# power_supply.net
KiCad netlist of a schematic drawn in Altium Designer
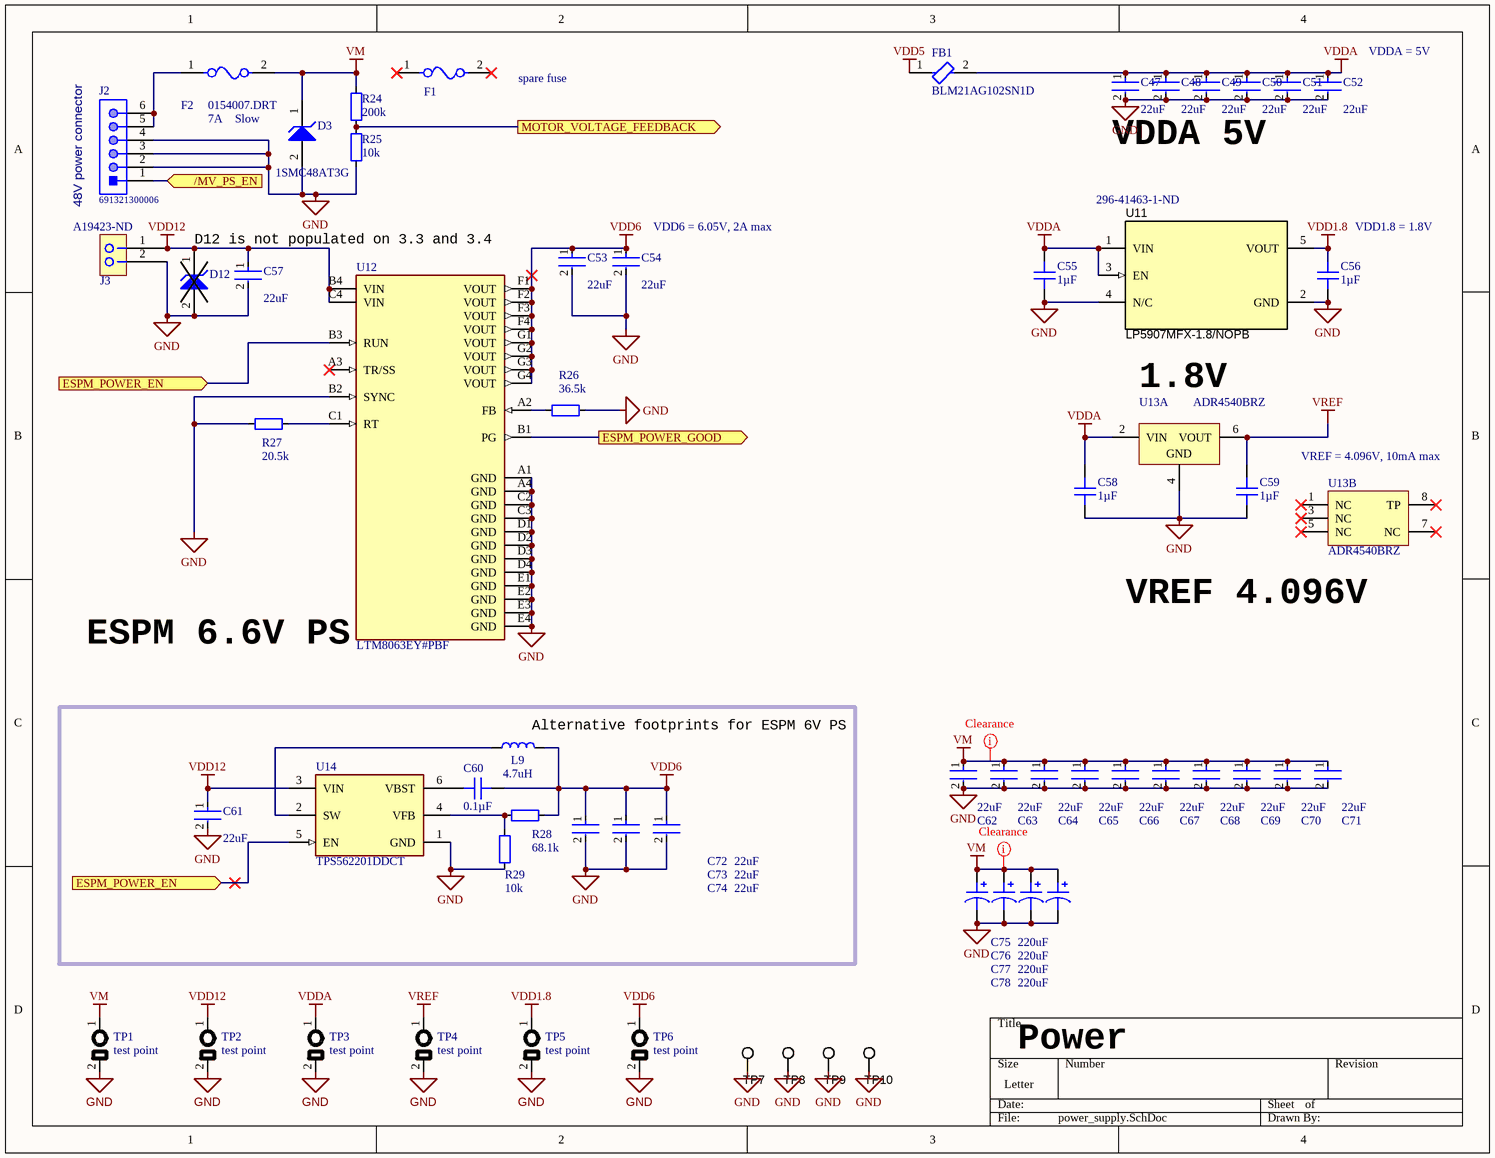
[diagram p0: power_supply.SchDoc]

(export (version "E")
  (design (tool "Eeschema 10.0.6"))
  (components
    (comp (ref "C47")
      (value "CL32B226MOJNNNE")
      (footprint "FP-CL32-IPC_B")
      (description "Cap Ceramic 22uF 16V X7R ±20% SMD 1210 +125°C Embossed T/R")
      (fields (field (name "CAPACITANCE") "22uF") (field (name "TOLERANCE") "20%"))
      (libsource (lib "Altium Content Vault") (part "b4654b650e69147ec39a6b967a45e02"))
    )
    (comp (ref "C48")
      (value "CL32B226MOJNNNE")
      (footprint "FP-CL32-IPC_B")
      (description "Cap Ceramic 22uF 16V X7R ±20% SMD 1210 +125°C Embossed T/R")
      (fields (field (name "CAPACITANCE") "22uF") (field (name "TOLERANCE") "20%"))
      (libsource (lib "Altium Content Vault") (part "b4654b650e69147ec39a6b967a45e02"))
    )
    (comp (ref "C49")
      (value "CL32B226MOJNNNE")
      (footprint "FP-CL32-IPC_B")
      (description "Cap Ceramic 22uF 16V X7R ±20% SMD 1210 +125°C Embossed T/R")
      (fields (field (name "CAPACITANCE") "22uF") (field (name "TOLERANCE") "20%"))
      (libsource (lib "Altium Content Vault") (part "b4654b650e69147ec39a6b967a45e02"))
    )
    (comp (ref "C50")
      (value "CL32B226MOJNNNE")
      (footprint "FP-CL32-IPC_B")
      (description "Cap Ceramic 22uF 16V X7R ±20% SMD 1210 +125°C Embossed T/R")
      (fields (field (name "CAPACITANCE") "22uF") (field (name "TOLERANCE") "20%"))
      (libsource (lib "Altium Content Vault") (part "b4654b650e69147ec39a6b967a45e02"))
    )
    (comp (ref "C51")
      (value "CL32B226MOJNNNE")
      (footprint "FP-CL32-IPC_B")
      (description "Cap Ceramic 22uF 16V X7R ±20% SMD 1210 +125°C Embossed T/R")
      (fields (field (name "CAPACITANCE") "22uF") (field (name "TOLERANCE") "20%"))
      (libsource (lib "Altium Content Vault") (part "b4654b650e69147ec39a6b967a45e02"))
    )
    (comp (ref "C52")
      (value "CL32B226MOJNNNE")
      (footprint "FP-CL32-IPC_B")
      (description "Cap Ceramic 22uF 16V X7R ±20% SMD 1210 +125°C Embossed T/R")
      (fields (field (name "CAPACITANCE") "22uF") (field (name "TOLERANCE") "20%"))
      (libsource (lib "Altium Content Vault") (part "b4654b650e69147ec39a6b967a45e02"))
    )
    (comp (ref "C53")
      (value "CL32B226MOJNNNE")
      (footprint "FP-CL32-IPC_B")
      (description "Cap Ceramic 22uF 16V X7R ±20% SMD 1210 +125°C Embossed T/R")
      (fields (field (name "CAPACITANCE") "22uF") (field (name "TOLERANCE") "20%"))
      (libsource (lib "Altium Content Vault") (part "b4654b650e69147ec39a6b967a45e02"))
    )
    (comp (ref "C54")
      (value "CL32B226MOJNNNE")
      (footprint "FP-CL32-IPC_B")
      (description "Cap Ceramic 22uF 16V X7R ±20% SMD 1210 +125°C Embossed T/R")
      (fields (field (name "CAPACITANCE") "22uF") (field (name "TOLERANCE") "20%"))
      (libsource (lib "Altium Content Vault") (part "b4654b650e69147ec39a6b967a45e02"))
    )
    (comp (ref "C55")
      (value "1µF")
      (footprint "FP-GRM155-0_05-IPC_B")
      (description "CAP CER 1UF 6.3V X7R 0402")
      (fields
        (field (name "PART NUMBER") "GRM155R70J105KA12J")
        (field (name "MANUFACTURER") "Murata Electronics")
      )
      (libsource (lib "Celestial Altium Library - altium_library") (part "Capacitor"))
    )
    (comp (ref "C56")
      (value "1µF")
      (footprint "FP-GRM155-0_05-IPC_B")
      (description "CAP CER 1UF 6.3V X7R 0402")
      (fields
        (field (name "PART NUMBER") "GRM155R70J105KA12J")
        (field (name "MANUFACTURER") "Murata Electronics")
      )
      (libsource (lib "Celestial Altium Library - altium_library") (part "Capacitor"))
    )
    (comp (ref "C57")
      (value "CL32B226MOJNNNE")
      (footprint "FP-CL32-IPC_B")
      (description "Cap Ceramic 22uF 16V X7R ±20% SMD 1210 +125°C Embossed T/R")
      (fields (field (name "CAPACITANCE") "22uF") (field (name "TOLERANCE") "20%"))
      (libsource (lib "Altium Content Vault") (part "b4654b650e69147ec39a6b967a45e02"))
    )
    (comp (ref "C58")
      (value "1µF")
      (footprint "FP-GRM155-0_05-IPC_B")
      (description "CAP CER 1UF 6.3V X7R 0402")
      (fields
        (field (name "PART NUMBER") "GRM155R70J105KA12J")
        (field (name "MANUFACTURER") "Murata Electronics")
      )
      (libsource (lib "Celestial Altium Library - altium_library") (part "Capacitor"))
    )
    (comp (ref "C59")
      (value "1µF")
      (footprint "FP-GRM155-0_05-IPC_B")
      (description "CAP CER 1UF 6.3V X7R 0402")
      (fields
        (field (name "PART NUMBER") "GRM155R70J105KA12J")
        (field (name "MANUFACTURER") "Murata Electronics")
      )
      (libsource (lib "Celestial Altium Library - altium_library") (part "Capacitor"))
    )
    (comp (ref "C60")
      (value "0.1µF")
      (footprint "FP-GRM155-0_05-IPC_B")
      (description "CAP CER 0.1UF 25V X7R 0402")
      (fields (field (name "MANUFACTURER") "AVX Corporation") (field (name "PART NUMBER") "04023C104KAT2A"))
      (libsource (lib "Celestial Altium Library - altium_library") (part "Capacitor"))
    )
    (comp (ref "C61")
      (value "CL32B226MOJNNNE")
      (footprint "FP-CL32-IPC_B")
      (description "Cap Ceramic 22uF 16V X7R ±20% SMD 1210 +125°C Embossed T/R")
      (fields (field (name "CAPACITANCE") "22uF") (field (name "TOLERANCE") "20%"))
      (libsource (lib "Altium Content Vault") (part "b4654b650e69147ec39a6b967a45e02"))
    )
    (comp (ref "C62")
      (value "KRM55WR72A226MH01L")
      (footprint "FP-KRM55W-6_1_5_3_6_7_1_2-MFG")
      (description "CAP CER 22UF 100V X7R SMD")
      (fields (field (name "CAPACITANCE") "22uF") (field (name "TOLERANCE") "20%"))
      (libsource (lib "Altium Content Vault") (part "02cd4be3c70576c341d710602a673aa"))
    )
    (comp (ref "C63")
      (value "KRM55WR72A226MH01L")
      (footprint "FP-KRM55W-6_1_5_3_6_7_1_2-MFG")
      (description "CAP CER 22UF 100V X7R SMD")
      (fields (field (name "CAPACITANCE") "22uF") (field (name "TOLERANCE") "20%"))
      (libsource (lib "Altium Content Vault") (part "02cd4be3c70576c341d710602a673aa"))
    )
    (comp (ref "C64")
      (value "KRM55WR72A226MH01L")
      (footprint "FP-KRM55W-6_1_5_3_6_7_1_2-MFG")
      (description "CAP CER 22UF 100V X7R SMD")
      (fields (field (name "CAPACITANCE") "22uF") (field (name "TOLERANCE") "20%"))
      (libsource (lib "Altium Content Vault") (part "02cd4be3c70576c341d710602a673aa"))
    )
    (comp (ref "C65")
      (value "KRM55WR72A226MH01L")
      (footprint "FP-KRM55W-6_1_5_3_6_7_1_2-MFG")
      (description "CAP CER 22UF 100V X7R SMD")
      (fields (field (name "CAPACITANCE") "22uF") (field (name "TOLERANCE") "20%"))
      (libsource (lib "Altium Content Vault") (part "02cd4be3c70576c341d710602a673aa"))
    )
    (comp (ref "C66")
      (value "KRM55WR72A226MH01L")
      (footprint "FP-KRM55W-6_1_5_3_6_7_1_2-MFG")
      (description "CAP CER 22UF 100V X7R SMD")
      (fields (field (name "CAPACITANCE") "22uF") (field (name "TOLERANCE") "20%"))
      (libsource (lib "Altium Content Vault") (part "02cd4be3c70576c341d710602a673aa"))
    )
    (comp (ref "C67")
      (value "KRM55WR72A226MH01L")
      (footprint "FP-KRM55W-6_1_5_3_6_7_1_2-MFG")
      (description "CAP CER 22UF 100V X7R SMD")
      (fields (field (name "CAPACITANCE") "22uF") (field (name "TOLERANCE") "20%"))
      (libsource (lib "Altium Content Vault") (part "02cd4be3c70576c341d710602a673aa"))
    )
    (comp (ref "C68")
      (value "KRM55WR72A226MH01L")
      (footprint "FP-KRM55W-6_1_5_3_6_7_1_2-MFG")
      (description "CAP CER 22UF 100V X7R SMD")
      (fields (field (name "CAPACITANCE") "22uF") (field (name "TOLERANCE") "20%"))
      (libsource (lib "Altium Content Vault") (part "02cd4be3c70576c341d710602a673aa"))
    )
    (comp (ref "C69")
      (value "KRM55WR72A226MH01L")
      (footprint "FP-KRM55W-6_1_5_3_6_7_1_2-MFG")
      (description "CAP CER 22UF 100V X7R SMD")
      (fields (field (name "CAPACITANCE") "22uF") (field (name "TOLERANCE") "20%"))
      (libsource (lib "Altium Content Vault") (part "02cd4be3c70576c341d710602a673aa"))
    )
    (comp (ref "C70")
      (value "KRM55WR72A226MH01L")
      (footprint "FP-KRM55W-6_1_5_3_6_7_1_2-MFG")
      (description "CAP CER 22UF 100V X7R SMD")
      (fields (field (name "CAPACITANCE") "22uF") (field (name "TOLERANCE") "20%"))
      (libsource (lib "Altium Content Vault") (part "02cd4be3c70576c341d710602a673aa"))
    )
    (comp (ref "C71")
      (value "KRM55WR72A226MH01L")
      (footprint "FP-KRM55W-6_1_5_3_6_7_1_2-MFG")
      (description "CAP CER 22UF 100V X7R SMD")
      (fields (field (name "CAPACITANCE") "22uF") (field (name "TOLERANCE") "20%"))
      (libsource (lib "Altium Content Vault") (part "02cd4be3c70576c341d710602a673aa"))
    )
    (comp (ref "C72")
      (value "CL32B226MOJNNNE")
      (footprint "FP-CL32-IPC_B")
      (description "Cap Ceramic 22uF 16V X7R ±20% SMD 1210 +125°C Embossed T/R")
      (fields (field (name "CAPACITANCE") "22uF") (field (name "TOLERANCE") "20%"))
      (libsource (lib "Altium Content Vault") (part "b4654b650e69147ec39a6b967a45e02"))
    )
    (comp (ref "C73")
      (value "CL32B226MOJNNNE")
      (footprint "FP-CL32-IPC_B")
      (description "Cap Ceramic 22uF 16V X7R ±20% SMD 1210 +125°C Embossed T/R")
      (fields (field (name "CAPACITANCE") "22uF") (field (name "TOLERANCE") "20%"))
      (libsource (lib "Altium Content Vault") (part "b4654b650e69147ec39a6b967a45e02"))
    )
    (comp (ref "C74")
      (value "CL32B226MOJNNNE")
      (footprint "FP-CL32-IPC_B")
      (description "Cap Ceramic 22uF 16V X7R ±20% SMD 1210 +125°C Embossed T/R")
      (fields (field (name "CAPACITANCE") "22uF") (field (name "TOLERANCE") "20%"))
      (libsource (lib "Altium Content Vault") (part "b4654b650e69147ec39a6b967a45e02"))
    )
    (comp (ref "C75")
      (value "~")
      (footprint "100TXW220MEFC10X40_horizontal")
      (description "TXW Series 100 V 220 uF 10 x 40 mm LS=5 mm Radial Aluminum Electrolytic")
      (fields
        (field (name "MANUFACTURER") "Rubycon")
        (field (name "MANUFACTURER PART NUMBER") "100TXW220MEFC10X40")
        (field (name "CAPACITANCE") "220uF")
      )
      (libsource (lib "dvrk-s-pwm_2") (part "Polarised Capacitor"))
    )
    (comp (ref "C76")
      (value "~")
      (footprint "100TXW220MEFC10X40_horizontal")
      (description "TXW Series 100 V 220 uF 10 x 40 mm LS=5 mm Radial Aluminum Electrolytic")
      (fields
        (field (name "MANUFACTURER") "Rubycon")
        (field (name "MANUFACTURER PART NUMBER") "100TXW220MEFC10X40")
        (field (name "CAPACITANCE") "220uF")
      )
      (libsource (lib "dvrk-s-pwm_2") (part "Polarised Capacitor"))
    )
    (comp (ref "C77")
      (value "~")
      (footprint "100TXW220MEFC10X40_horizontal")
      (description "TXW Series 100 V 220 uF 10 x 40 mm LS=5 mm Radial Aluminum Electrolytic")
      (fields
        (field (name "MANUFACTURER") "Rubycon")
        (field (name "MANUFACTURER PART NUMBER") "100TXW220MEFC10X40")
        (field (name "CAPACITANCE") "220uF")
      )
      (libsource (lib "dvrk-s-pwm_2") (part "Polarised Capacitor"))
    )
    (comp (ref "C78")
      (value "~")
      (footprint "100TXW220MEFC10X40_horizontal")
      (description "TXW Series 100 V 220 uF 10 x 40 mm LS=5 mm Radial Aluminum Electrolytic")
      (fields
        (field (name "MANUFACTURER") "Rubycon")
        (field (name "MANUFACTURER PART NUMBER") "100TXW220MEFC10X40")
        (field (name "CAPACITANCE") "220uF")
      )
      (libsource (lib "dvrk-s-pwm_2") (part "Polarised Capacitor"))
    )
    (comp (ref "D3")
      (value "1SMC48AT3G")
      (footprint "ONSC-SMC-2-403-03_V")
      (fields (field (name "MANUFACTURER") "On Semiconductor"))
      (libsource (lib "Altium Content Vault") (part "ONSC-K1A2-2"))
    )
    (comp (ref "D12")
      (value "1SMA12AT3G")
      (footprint "ONSC-SMA-2-403D-02_F_V")
      (description "400 W Peak Power Zener Transient Voltage Suppressor, 2-Pin SMA, Pb-Free, Tape and Reel")
      (fields (field (name "MANUFACTURER") "On Semiconductor"))
      (libsource (lib "Altium Content Vault") (part "ONSC-K1A2-2"))
    )
    (comp (ref "F1")
      (value "0154007.DRT")
      (footprint "FP-0154-MFG")
      (description "FUSE BRD MNT 7A 72VAC 60VDC 2SMD")
      (fields
        (field (name "OCTOPART") "https://octopart.com/0154007.drt-littelfuse-19644006")
        (field (name "MANUFACTURER") "Littelfuse Inc")
      )
      (libsource (lib "Altium Content Vault") (part "5bcf9b9f640e542cf0359d10258e979"))
    )
    (comp (ref "F2")
      (value "0154007.DRT")
      (footprint "FP-0154-MFG")
      (description "FUSE BRD MNT 7A 72VAC 60VDC 2SMD")
      (fields
        (field (name "FUSE CURRENT") "7A")
        (field (name "FUSE BLOW SPEED") "Slow")
        (field (name "OCTOPART") "https://octopart.com/0154007.drt-littelfuse-19644006")
        (field (name "MANUFACTURER") "Littelfuse Inc")
      )
      (libsource (lib "Altium Content Vault") (part "5bcf9b9f640e542cf0359d10258e979"))
    )
    (comp (ref "FB1")
      (value "BLM21AG102SN1D")
      (footprint "FP-BLM21-0_2-t0_85-e0_5-MFG")
      (description "Chip Ferrite Bead, 0805, 1000Ω @ 100MHz, 0.27Ω, 25%, 600mA")
      (fields (field (name "TOLERANCE") "25%"))
      (libsource (lib "Altium Content Vault") (part "5f30dd21d616792df468990f7003faa"))
    )
    (comp (ref "J2")
      (value "691321300006")
      (footprint "691321300006")
      (description "Serie 321 - 3.81mm Vertical PCB Header WR-TBL, 6 pin")
      (fields (field (name "MANUFACTURER") "Wurth Elektronik") (field (name "PUBLISHER") "WurthElektronik"))
      (libsource (lib "Altium Content Vault") (part "WE-CN-1P-M-R6"))
    )
    (comp (ref "J3")
      (value "Substitute with tyco 640457-2")
      (footprint "HDR-2x1-100")
      (fields
        (field (name "MANUFACTURER") "TE Connectivity")
        (field (name "MANUFACTURER PART NUMBER") "640457-2")
        (field (name "SUPPLIER PART NUMBER 1") "A19423-ND")
      )
      (libsource (lib "dvrk-s-pwm") (part "HEADER 2"))
    )
    (comp (ref "L9")
      (value "4.7uH")
      (footprint "INDUCTOR-XAL7030")
      (libsource (lib "FPGA") (part "INDUCTOR"))
    )
    (comp (ref "R24")
      (value "200k")
      (footprint "FP-CRCW0402-e3-IPC_B")
      (description "Resistor")
      (fields (field (name "Comment") "Res_0402"))
      (libsource (lib "SCH_Passive") (part "Res_0402"))
    )
    (comp (ref "R25")
      (value "10k")
      (footprint "FP-CRCW0402-e3-IPC_B")
      (description "Resistor")
      (fields (field (name "Comment") "Res_0402"))
      (libsource (lib "SCH_Passive") (part "Res_0402"))
    )
    (comp (ref "R26")
      (value "36.5k")
      (footprint "FP-CRCW0402-e3-IPC_B")
      (description "Resistor")
      (fields (field (name "Comment") "Res_0402"))
      (libsource (lib "") (part "Res_0402_1"))
    )
    (comp (ref "R27")
      (value "20.5k")
      (footprint "FP-CRCW0402-e3-IPC_B")
      (description "Resistor")
      (fields (field (name "Comment") "Res_0402"))
      (libsource (lib "") (part "Res_0402_1"))
    )
    (comp (ref "R28")
      (value "68.1k")
      (footprint "FP-CRCW0402-e3-IPC_B")
      (description "Resistor")
      (fields (field (name "Comment") "Res_0402"))
      (libsource (lib "") (part "Res_0402_1"))
    )
    (comp (ref "R29")
      (value "10k")
      (footprint "FP-CRCW0402-e3-IPC_B")
      (description "Resistor")
      (fields (field (name "Comment") "Res_0402"))
      (libsource (lib "SCH_Passive") (part "Res_0402"))
    )
    (comp (ref "TP1")
      (value "test point")
      (footprint "TP_GND")
      (libsource (lib "dvrk-s-pwm") (part "TP_GND"))
    )
    (comp (ref "TP2")
      (value "test point")
      (footprint "TP_GND")
      (libsource (lib "dvrk-s-pwm") (part "TP_GND"))
    )
    (comp (ref "TP3")
      (value "test point")
      (footprint "TP_GND")
      (libsource (lib "dvrk-s-pwm") (part "TP_GND"))
    )
    (comp (ref "TP4")
      (value "test point")
      (footprint "TP_GND")
      (libsource (lib "dvrk-s-pwm") (part "TP_GND"))
    )
    (comp (ref "TP5")
      (value "test point")
      (footprint "TP_GND")
      (libsource (lib "dvrk-s-pwm") (part "TP_GND"))
    )
    (comp (ref "TP6")
      (value "test point")
      (footprint "TP_GND")
      (libsource (lib "dvrk-s-pwm") (part "TP_GND"))
    )
    (comp (ref "TP7")
      (value "5016")
      (footprint "Testpoint_Keystone_Compact")
      (description "Test Point, Compact, SMT")
      (fields (field (name "MANUFACTURER") "Keystone") (field (name "PUBLISHER") "Texas Instruments"))
      (libsource (lib "dvrk-s-pwm") (part "5016"))
    )
    (comp (ref "TP8")
      (value "5016")
      (footprint "Testpoint_Keystone_Compact")
      (description "Test Point, Compact, SMT")
      (fields (field (name "MANUFACTURER") "Keystone") (field (name "PUBLISHER") "Texas Instruments"))
      (libsource (lib "dvrk-s-pwm") (part "5016"))
    )
    (comp (ref "TP9")
      (value "5016")
      (footprint "Testpoint_Keystone_Compact")
      (description "Test Point, Compact, SMT")
      (fields (field (name "MANUFACTURER") "Keystone") (field (name "PUBLISHER") "Texas Instruments"))
      (libsource (lib "dvrk-s-pwm") (part "5016"))
    )
    (comp (ref "TP10")
      (value "5016")
      (footprint "Testpoint_Keystone_Compact")
      (description "Test Point, Compact, SMT")
      (fields (field (name "MANUFACTURER") "Keystone") (field (name "PUBLISHER") "Texas Instruments"))
      (libsource (lib "dvrk-s-pwm") (part "5016"))
    )
    (comp (ref "U11")
      (value "LP5907MFX-1.8/NOPB")
      (footprint "DBV0005A_N")
      (description "Ultra Low Noise, 250mA Linear Regulator")
      (fields
        (field (name "MANUFACTURER") "Texas Instruments")
        (field (name "SUPPLIER PART NUMBER 1") "296-41463-1-ND")
        (field (name "SYMBOLCREATOR") "a0799628")
        (field (name "PUBLISHER") "Texas Instruments")
      )
      (libsource (lib "dvrk-s-pwm") (part "LP5907MFX-3.3/NOPB"))
    )
    (comp (ref "U12")
      (value "LTM8063EY#PBF")
      (footprint "FP-BGA-28-05-08-1517-MFG")
      (description "DC DC CONVERTER 0.8-15V")
      (fields
        (field (name "OCTOPART") "https://octopart.com/ltm8063ey%23pbf-analog+devices-88947122")
        (field (name "MANUFACTURER") "Analog Devices")
      )
      (libsource (lib "Altium Content Vault") (part "b54610757978533170b9aabd89f6d2c"))
    )
    (comp (ref "U13")
      (value "ADR4540BRZ")
      (footprint "ADI-R-8_M")
      (fields (field (name "MANUFACTURER") "Analog Devices"))
      (libsource (lib "Altium Content Vault") (part "ADI-ADR45xx-R-8"))
    )
    (comp (ref "U14")
      (value "TPS562201DDCT")
      (footprint "FP-DDC0006A-IPC_C")
      (description "IC REG BUCK ADJ 2A TSOT23-6")
      (fields
        (field (name "OCTOPART") "https://octopart.com/tps562201ddct-texas+instruments-68059584")
        (field (name "MANUFACTURER") "Texas Instruments")
      )
      (libsource (lib "Altium Content Vault") (part "06d79c7d29d628b4662ce6edb459819"))
    )
  )
  (nets
    (net (code "1") (name "/ESPM_POWER_EN") (class "Default")
      (node (ref "U12") (pin "B3") (pinfunction "RUN_B3") (pintype "input"))
      (node (ref "U14") (pin "5") (pinfunction "EN_5") (pintype "input"))
    )
    (net (code "2") (name "/ESPM_POWER_GOOD") (class "Default")
      (node (ref "U12") (pin "B1") (pinfunction "PG_B1") (pintype "output"))
    )
    (net (code "3") (name "/MOTOR_VOLTAGE_FEEDBACK") (class "Default")
      (node (ref "R24") (pin "1") (pinfunction "1_1") (pintype "passive"))
      (node (ref "R25") (pin "2") (pinfunction "2_2") (pintype "passive"))
    )
    (net (code "4") (name "/{slash}MV_PS_EN") (class "Default")
      (node (ref "J2") (pin "1") (pinfunction "1_1") (pintype "passive"))
    )
    (net (code "5") (name "GND") (class "Default")
      (node (ref "C47") (pin "2") (pinfunction "2_2") (pintype "passive"))
      (node (ref "C48") (pin "2") (pinfunction "2_2") (pintype "passive"))
      (node (ref "C49") (pin "2") (pinfunction "2_2") (pintype "passive"))
      (node (ref "C50") (pin "2") (pinfunction "2_2") (pintype "passive"))
      (node (ref "C51") (pin "2") (pinfunction "2_2") (pintype "passive"))
      (node (ref "C52") (pin "2") (pinfunction "2_2") (pintype "passive"))
      (node (ref "C53") (pin "2") (pinfunction "2_2") (pintype "passive"))
      (node (ref "C54") (pin "2") (pinfunction "2_2") (pintype "passive"))
      (node (ref "C55") (pin "1") (pinfunction "1_1") (pintype "passive"))
      (node (ref "C56") (pin "1") (pinfunction "1_1") (pintype "passive"))
      (node (ref "C57") (pin "2") (pinfunction "2_2") (pintype "passive"))
      (node (ref "C58") (pin "1") (pinfunction "1_1") (pintype "passive"))
      (node (ref "C59") (pin "1") (pinfunction "1_1") (pintype "passive"))
      (node (ref "C61") (pin "2") (pinfunction "2_2") (pintype "passive"))
      (node (ref "C62") (pin "2") (pinfunction "2_2") (pintype "passive"))
      (node (ref "C63") (pin "2") (pinfunction "2_2") (pintype "passive"))
      (node (ref "C64") (pin "2") (pinfunction "2_2") (pintype "passive"))
      (node (ref "C65") (pin "2") (pinfunction "2_2") (pintype "passive"))
      (node (ref "C66") (pin "2") (pinfunction "2_2") (pintype "passive"))
      (node (ref "C67") (pin "2") (pinfunction "2_2") (pintype "passive"))
      (node (ref "C68") (pin "2") (pinfunction "2_2") (pintype "passive"))
      (node (ref "C69") (pin "2") (pinfunction "2_2") (pintype "passive"))
      (node (ref "C70") (pin "2") (pinfunction "2_2") (pintype "passive"))
      (node (ref "C71") (pin "2") (pinfunction "2_2") (pintype "passive"))
      (node (ref "C72") (pin "2") (pinfunction "2_2") (pintype "passive"))
      (node (ref "C73") (pin "2") (pinfunction "2_2") (pintype "passive"))
      (node (ref "C74") (pin "2") (pinfunction "2_2") (pintype "passive"))
      (node (ref "C75") (pin "2") (pinfunction "2_2") (pintype "passive"))
      (node (ref "C76") (pin "2") (pinfunction "2_2") (pintype "passive"))
      (node (ref "C77") (pin "2") (pinfunction "2_2") (pintype "passive"))
      (node (ref "C78") (pin "2") (pinfunction "2_2") (pintype "passive"))
      (node (ref "D12") (pin "2") (pinfunction "A_2") (pintype "passive"))
      (node (ref "D3") (pin "2") (pinfunction "A_2") (pintype "passive"))
      (node (ref "J2") (pin "2") (pinfunction "2_2") (pintype "passive"))
      (node (ref "J2") (pin "3") (pinfunction "3_3") (pintype "passive"))
      (node (ref "J2") (pin "4") (pinfunction "4_4") (pintype "passive"))
      (node (ref "J3") (pin "2") (pinfunction "2_2") (pintype "passive"))
      (node (ref "R25") (pin "1") (pinfunction "1_1") (pintype "passive"))
      (node (ref "R26") (pin "1") (pinfunction "1_1") (pintype "passive"))
      (node (ref "R27") (pin "2") (pinfunction "2_2") (pintype "passive"))
      (node (ref "R29") (pin "1") (pinfunction "1_1") (pintype "passive"))
      (node (ref "TP1") (pin "2") (pinfunction "gnd_2") (pintype "passive"))
      (node (ref "TP10") (pin "1") (pintype "passive"))
      (node (ref "TP2") (pin "2") (pinfunction "gnd_2") (pintype "passive"))
      (node (ref "TP3") (pin "2") (pinfunction "gnd_2") (pintype "passive"))
      (node (ref "TP4") (pin "2") (pinfunction "gnd_2") (pintype "passive"))
      (node (ref "TP5") (pin "2") (pinfunction "gnd_2") (pintype "passive"))
      (node (ref "TP6") (pin "2") (pinfunction "gnd_2") (pintype "passive"))
      (node (ref "TP7") (pin "1") (pintype "passive"))
      (node (ref "TP8") (pin "1") (pintype "passive"))
      (node (ref "TP9") (pin "1") (pintype "passive"))
      (node (ref "U11") (pin "2") (pinfunction "GND_2") (pintype "power_in"))
      (node (ref "U11") (pin "4") (pinfunction "N/C_4") (pintype "passive"))
      (node (ref "U12") (pin "A1") (pinfunction "GND_A1") (pintype "power_in"))
      (node (ref "U12") (pin "A4") (pinfunction "GND_A4") (pintype "power_in"))
      (node (ref "U12") (pin "B2") (pinfunction "SYNC_B2") (pintype "input"))
      (node (ref "U12") (pin "C2") (pinfunction "GND_C2") (pintype "power_in"))
      (node (ref "U12") (pin "C3") (pinfunction "GND_C3") (pintype "power_in"))
      (node (ref "U12") (pin "D1") (pinfunction "GND_D1") (pintype "power_in"))
      (node (ref "U12") (pin "D2") (pinfunction "GND_D2") (pintype "power_in"))
      (node (ref "U12") (pin "D3") (pinfunction "GND_D3") (pintype "power_in"))
      (node (ref "U12") (pin "D4") (pinfunction "GND_D4") (pintype "power_in"))
      (node (ref "U12") (pin "E1") (pinfunction "GND_E1") (pintype "power_in"))
      (node (ref "U12") (pin "E2") (pinfunction "GND_E2") (pintype "power_in"))
      (node (ref "U12") (pin "E3") (pinfunction "GND_E3") (pintype "power_in"))
      (node (ref "U12") (pin "E4") (pinfunction "GND_E4") (pintype "power_in"))
      (node (ref "U13") (pin "4") (pinfunction "GND_4") (pintype "power_in"))
      (node (ref "U14") (pin "1") (pinfunction "GND_1") (pintype "power_in"))
    )
    (net (code "6") (name "Net-(F2-Pad1)") (class "Default")
      (node (ref "F2") (pin "1") (pinfunction "1_1") (pintype "passive"))
      (node (ref "J2") (pin "5") (pinfunction "5_5") (pintype "passive"))
      (node (ref "J2") (pin "6") (pinfunction "6_6") (pintype "passive"))
    )
    (net (code "7") (name "Net-(U12-FB)") (class "Default")
      (node (ref "R26") (pin "2") (pinfunction "2_2") (pintype "passive"))
      (node (ref "U12") (pin "A2") (pinfunction "FB_A2") (pintype "input"))
    )
    (net (code "8") (name "Net-(U12-RT)") (class "Default")
      (node (ref "R27") (pin "1") (pinfunction "1_1") (pintype "passive"))
      (node (ref "U12") (pin "C1") (pinfunction "RT_C1") (pintype "input"))
    )
    (net (code "9") (name "Net-(U14-SW)") (class "Default")
      (node (ref "L9") (pin "1") (pintype "passive"))
      (node (ref "U14") (pin "2") (pinfunction "SW_2") (pintype "passive"))
    )
    (net (code "10") (name "Net-(U14-VBST)") (class "Default")
      (node (ref "C60") (pin "1") (pinfunction "1_1") (pintype "passive"))
      (node (ref "U14") (pin "6") (pinfunction "VBST_6") (pintype "power_in"))
    )
    (net (code "11") (name "Net-(U14-VFB)") (class "Default")
      (node (ref "R28") (pin "2") (pinfunction "2_2") (pintype "passive"))
      (node (ref "R29") (pin "2") (pinfunction "2_2") (pintype "passive"))
      (node (ref "U14") (pin "4") (pinfunction "VFB_4") (pintype "passive"))
    )
    (net (code "12") (name "VDD1.8") (class "Default")
      (node (ref "C56") (pin "2") (pinfunction "2_2") (pintype "passive"))
      (node (ref "TP5") (pin "1") (pintype "passive"))
      (node (ref "U11") (pin "5") (pinfunction "VOUT_5") (pintype "power_in"))
    )
    (net (code "13") (name "VDD5") (class "Default")
      (node (ref "FB1") (pin "1") (pinfunction "1_1") (pintype "passive"))
    )
    (net (code "14") (name "VDD6") (class "Default")
      (node (ref "C53") (pin "1") (pinfunction "1_1") (pintype "passive"))
      (node (ref "C54") (pin "1") (pinfunction "1_1") (pintype "passive"))
      (node (ref "C60") (pin "2") (pinfunction "2_2") (pintype "passive"))
      (node (ref "C72") (pin "1") (pinfunction "1_1") (pintype "passive"))
      (node (ref "C73") (pin "1") (pinfunction "1_1") (pintype "passive"))
      (node (ref "C74") (pin "1") (pinfunction "1_1") (pintype "passive"))
      (node (ref "L9") (pin "2") (pintype "passive"))
      (node (ref "R28") (pin "1") (pinfunction "1_1") (pintype "passive"))
      (node (ref "TP6") (pin "1") (pintype "passive"))
      (node (ref "U12") (pin "F1") (pinfunction "VOUT_F1") (pintype "output"))
      (node (ref "U12") (pin "F2") (pinfunction "VOUT_F2") (pintype "output"))
      (node (ref "U12") (pin "F3") (pinfunction "VOUT_F3") (pintype "output"))
      (node (ref "U12") (pin "F4") (pinfunction "VOUT_F4") (pintype "output"))
      (node (ref "U12") (pin "G1") (pinfunction "VOUT_G1") (pintype "output"))
      (node (ref "U12") (pin "G2") (pinfunction "VOUT_G2") (pintype "output"))
      (node (ref "U12") (pin "G3") (pinfunction "VOUT_G3") (pintype "output"))
      (node (ref "U12") (pin "G4") (pinfunction "VOUT_G4") (pintype "output"))
    )
    (net (code "15") (name "VDD12") (class "Default")
      (node (ref "C57") (pin "1") (pinfunction "1_1") (pintype "passive"))
      (node (ref "C61") (pin "1") (pinfunction "1_1") (pintype "passive"))
      (node (ref "D12") (pin "1") (pinfunction "K_1") (pintype "passive"))
      (node (ref "J3") (pin "1") (pinfunction "1_1") (pintype "passive"))
      (node (ref "TP2") (pin "1") (pintype "passive"))
      (node (ref "U12") (pin "B4") (pinfunction "VIN_B4") (pintype "power_in"))
      (node (ref "U12") (pin "C4") (pinfunction "VIN_C4") (pintype "power_in"))
      (node (ref "U14") (pin "3") (pinfunction "VIN_3") (pintype "power_in"))
    )
    (net (code "16") (name "VDDA") (class "Default")
      (node (ref "C47") (pin "1") (pinfunction "1_1") (pintype "passive"))
      (node (ref "C48") (pin "1") (pinfunction "1_1") (pintype "passive"))
      (node (ref "C49") (pin "1") (pinfunction "1_1") (pintype "passive"))
      (node (ref "C50") (pin "1") (pinfunction "1_1") (pintype "passive"))
      (node (ref "C51") (pin "1") (pinfunction "1_1") (pintype "passive"))
      (node (ref "C52") (pin "1") (pinfunction "1_1") (pintype "passive"))
      (node (ref "C55") (pin "2") (pinfunction "2_2") (pintype "passive"))
      (node (ref "C58") (pin "2") (pinfunction "2_2") (pintype "passive"))
      (node (ref "FB1") (pin "2") (pinfunction "2_2") (pintype "passive"))
      (node (ref "TP3") (pin "1") (pintype "passive"))
      (node (ref "U11") (pin "1") (pinfunction "VIN_1") (pintype "power_in"))
      (node (ref "U11") (pin "3") (pinfunction "EN_3") (pintype "input"))
      (node (ref "U13") (pin "2") (pinfunction "VIN_2") (pintype "power_in"))
    )
    (net (code "17") (name "VM") (class "Default")
      (node (ref "C62") (pin "1") (pinfunction "1_1") (pintype "passive"))
      (node (ref "C63") (pin "1") (pinfunction "1_1") (pintype "passive"))
      (node (ref "C64") (pin "1") (pinfunction "1_1") (pintype "passive"))
      (node (ref "C65") (pin "1") (pinfunction "1_1") (pintype "passive"))
      (node (ref "C66") (pin "1") (pinfunction "1_1") (pintype "passive"))
      (node (ref "C67") (pin "1") (pinfunction "1_1") (pintype "passive"))
      (node (ref "C68") (pin "1") (pinfunction "1_1") (pintype "passive"))
      (node (ref "C69") (pin "1") (pinfunction "1_1") (pintype "passive"))
      (node (ref "C70") (pin "1") (pinfunction "1_1") (pintype "passive"))
      (node (ref "C71") (pin "1") (pinfunction "1_1") (pintype "passive"))
      (node (ref "C75") (pin "1") (pinfunction "1_1") (pintype "passive"))
      (node (ref "C76") (pin "1") (pinfunction "1_1") (pintype "passive"))
      (node (ref "C77") (pin "1") (pinfunction "1_1") (pintype "passive"))
      (node (ref "C78") (pin "1") (pinfunction "1_1") (pintype "passive"))
      (node (ref "D3") (pin "1") (pinfunction "K_1") (pintype "passive"))
      (node (ref "F2") (pin "2") (pinfunction "2_2") (pintype "passive"))
      (node (ref "R24") (pin "2") (pinfunction "2_2") (pintype "passive"))
      (node (ref "TP1") (pin "1") (pintype "passive"))
    )
    (net (code "18") (name "VREF") (class "Default")
      (node (ref "C59") (pin "2") (pinfunction "2_2") (pintype "passive"))
      (node (ref "TP4") (pin "1") (pintype "passive"))
      (node (ref "U13") (pin "6") (pinfunction "VOUT_6") (pintype "power_in"))
    )
    (net (code "19") (name "unconnected-(F1-Pad1)") (class "Default")
      (node (ref "F1") (pin "1") (pinfunction "1_1") (pintype "passive+no_connect"))
    )
    (net (code "20") (name "unconnected-(F1-Pad2)") (class "Default")
      (node (ref "F1") (pin "2") (pinfunction "2_2") (pintype "passive+no_connect"))
    )
    (net (code "21") (name "unconnected-(U12-TR{slash}SS-PadA3)") (class "Default")
      (node (ref "U12") (pin "A3") (pinfunction "TR/SS_A3") (pintype "input+no_connect"))
    )
    (net (code "22") (name "unconnected-(U13B-NC-Pad1)") (class "Default")
      (node (ref "U13") (pin "1") (pinfunction "NC_1") (pintype "passive+no_connect"))
    )
    (net (code "23") (name "unconnected-(U13B-NC-Pad3)") (class "Default")
      (node (ref "U13") (pin "3") (pinfunction "NC_3") (pintype "passive+no_connect"))
    )
    (net (code "24") (name "unconnected-(U13B-NC-Pad5)") (class "Default")
      (node (ref "U13") (pin "5") (pinfunction "NC_5") (pintype "passive+no_connect"))
    )
    (net (code "25") (name "unconnected-(U13B-NC-Pad7)") (class "Default")
      (node (ref "U13") (pin "7") (pinfunction "NC_7") (pintype "passive+no_connect"))
    )
    (net (code "26") (name "unconnected-(U13B-TP-Pad8)") (class "Default")
      (node (ref "U13") (pin "8") (pinfunction "TP_8") (pintype "passive+no_connect"))
    )
  )
)
